# Power_Management.net
KiCad netlist of a schematic drawn in Altium Designer
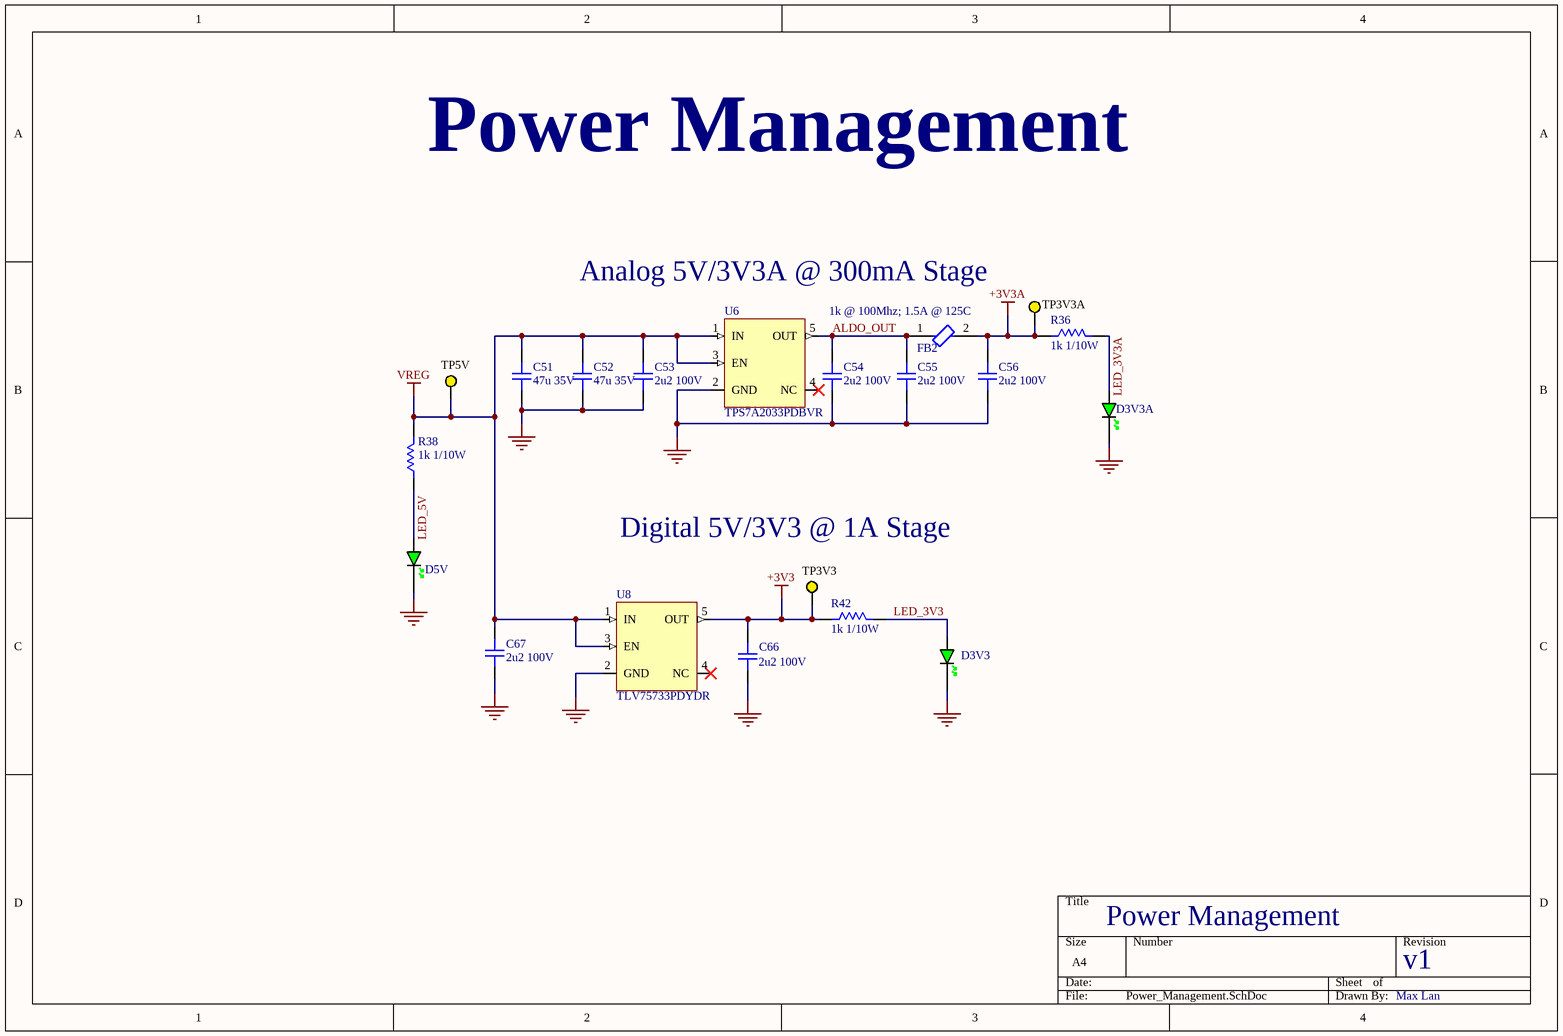
[diagram p0: Power_Management.SchDoc]

(export (version "E")
  (design (tool "Eeschema 10.0.6"))
  (components
    (comp (ref "C51")
      (value "47u 35V")
      (footprint "CAP_2220")
      (description "MLCC - SMD/SMT 2220 35VDC 47uF 20% X7R")
      (libsource (lib "Schematic-Lib-PhilsLab") (part "C5750X7R1V476M230KC"))
    )
    (comp (ref "C52")
      (value "47u 35V")
      (footprint "CAP_2220")
      (description "MLCC - SMD/SMT 2220 35VDC 47uF 20% X7R")
      (libsource (lib "Schematic-Lib-PhilsLab") (part "C5750X7R1V476M230KC"))
    )
    (comp (ref "C53")
      (value "2u2 100V")
      (footprint "CAP_1210")
      (description "Multilayer Ceramic Capacitors MLCC - SMD/SMT 100V 2.2uF X7R 1210 5% AEC-Q200")
      (fields
        (field (name "MANUFACTURER") "KEMET")
        (field (name "MANUFACTURER PART NUMBER") "C1210C225J1RACAUTO")
      )
      (libsource (lib "Schematic-Lib-PhilsLab") (part "C1210C225J1RACAUTO"))
    )
    (comp (ref "C54")
      (value "2u2 100V")
      (footprint "CAP_1210")
      (description "Multilayer Ceramic Capacitors MLCC - SMD/SMT 100V 2.2uF X7R 1210 5% AEC-Q200")
      (fields
        (field (name "MANUFACTURER") "KEMET")
        (field (name "MANUFACTURER PART NUMBER") "C1210C225J1RACAUTO")
      )
      (libsource (lib "Schematic-Lib-PhilsLab") (part "C1210C225J1RACAUTO"))
    )
    (comp (ref "C55")
      (value "2u2 100V")
      (footprint "CAP_1210")
      (description "Multilayer Ceramic Capacitors MLCC - SMD/SMT 100V 2.2uF X7R 1210 5% AEC-Q200")
      (fields
        (field (name "MANUFACTURER") "KEMET")
        (field (name "MANUFACTURER PART NUMBER") "C1210C225J1RACAUTO")
      )
      (libsource (lib "Schematic-Lib-PhilsLab") (part "C1210C225J1RACAUTO"))
    )
    (comp (ref "C56")
      (value "2u2 100V")
      (footprint "CAP_1210")
      (description "Multilayer Ceramic Capacitors MLCC - SMD/SMT 100V 2.2uF X7R 1210 5% AEC-Q200")
      (fields
        (field (name "MANUFACTURER") "KEMET")
        (field (name "MANUFACTURER PART NUMBER") "C1210C225J1RACAUTO")
      )
      (libsource (lib "Schematic-Lib-PhilsLab") (part "C1210C225J1RACAUTO"))
    )
    (comp (ref "C66")
      (value "2u2 100V")
      (footprint "CAP_1210")
      (description "Multilayer Ceramic Capacitors MLCC - SMD/SMT 100V 2.2uF X7R 1210 5% AEC-Q200")
      (fields
        (field (name "MANUFACTURER") "KEMET")
        (field (name "MANUFACTURER PART NUMBER") "C1210C225J1RACAUTO")
      )
      (libsource (lib "Schematic-Lib-PhilsLab") (part "C1210C225J1RACAUTO"))
    )
    (comp (ref "C67")
      (value "2u2 100V")
      (footprint "CAP_1210")
      (description "Multilayer Ceramic Capacitors MLCC - SMD/SMT 100V 2.2uF X7R 1210 5% AEC-Q200")
      (fields
        (field (name "MANUFACTURER") "KEMET")
        (field (name "MANUFACTURER PART NUMBER") "C1210C225J1RACAUTO")
      )
      (libsource (lib "Schematic-Lib-PhilsLab") (part "C1210C225J1RACAUTO"))
    )
    (comp (ref "D3V3")
      (value "GREEN")
      (footprint "LED_0603_GREEN")
      (description "LED 0603 GREEN SMD")
      (libsource (lib "Schematic-Lib-PhilsLab") (part "LED_0603_GREEN"))
    )
    (comp (ref "D3V3A")
      (value "GREEN")
      (footprint "LED_0603_GREEN")
      (description "LED 0603 GREEN SMD")
      (libsource (lib "Schematic-Lib-PhilsLab") (part "LED_0603_GREEN"))
    )
    (comp (ref "D5V")
      (value "GREEN")
      (footprint "LED_0603_GREEN")
      (description "LED 0603 GREEN SMD")
      (libsource (lib "Schematic-Lib-PhilsLab") (part "LED_0603_GREEN"))
    )
    (comp (ref "FB2")
      (value "1k @ 100Mhz; 1.5A @ 125C")
      (footprint "FP-MPZ2012-MFG")
      (description "FERRITE BEAD 1 KOHM 0805 1LN")
      (fields (field (name "TOLERANCE") "25%"))
      (libsource (lib "Altium Content Vault") (part "5f30dd21d616792df468990f7003faa"))
    )
    (comp (ref "R36")
      (value "1k 1/10W")
      (footprint "RES_0603")
      (description "Thick Film Resistors - SMD Res 0603 1k 1% 100mW TC100 low lead")
      (fields
        (field (name "MANUFACTURER") "Bourns")
        (field (name "MANUFACTURER PART NUMBER") "CR0603-FX-1001EPF")
      )
      (libsource (lib "Schematic-Lib-PhilsLab") (part "CR0603-FX-1001EPF"))
    )
    (comp (ref "R38")
      (value "1k 1/10W")
      (footprint "RES_0603")
      (description "Thick Film Resistors - SMD Res 0603 1k 1% 100mW TC100 low lead")
      (fields
        (field (name "MANUFACTURER") "Bourns")
        (field (name "MANUFACTURER PART NUMBER") "CR0603-FX-1001EPF")
      )
      (libsource (lib "Schematic-Lib-PhilsLab") (part "CR0603-FX-1001EPF"))
    )
    (comp (ref "R42")
      (value "1k 1/10W")
      (footprint "RES_0603")
      (description "Thick Film Resistors - SMD Res 0603 1k 1% 100mW TC100 low lead")
      (fields
        (field (name "MANUFACTURER") "Bourns")
        (field (name "MANUFACTURER PART NUMBER") "CR0603-FX-1001EPF")
      )
      (libsource (lib "Schematic-Lib-PhilsLab") (part "CR0603-FX-1001EPF"))
    )
    (comp (ref "TP3V3")
      (value "5014")
      (footprint "KSTN-5014_V")
      (description "Test Point, Yellow, Through Hole, RoHS, Bulk")
      (fields (field (name "MANUFACTURER") "Keystone"))
      (libsource (lib "Altium Content Vault") (part "TESTPOINT_YELLOW"))
    )
    (comp (ref "TP3V3A")
      (value "5014")
      (footprint "KSTN-5014_V")
      (description "Test Point, Yellow, Through Hole, RoHS, Bulk")
      (fields (field (name "MANUFACTURER") "Keystone"))
      (libsource (lib "Altium Content Vault") (part "TESTPOINT_YELLOW"))
    )
    (comp (ref "TP5V")
      (value "5014")
      (footprint "KSTN-5014_V")
      (description "Test Point, Yellow, Through Hole, RoHS, Bulk")
      (fields (field (name "MANUFACTURER") "Keystone"))
      (libsource (lib "Altium Content Vault") (part "TESTPOINT_YELLOW"))
    )
    (comp (ref "U6")
      (value "TPS7A2033PDBVR")
      (footprint "TPS7A2033PDBVR")
      (libsource (lib "Schematic-Lib-PhilsLab") (part "TPS7A2033PDBVR"))
    )
    (comp (ref "U8")
      (value "TLV75733PDYDR")
      (footprint "TLV75733PDYDR")
      (libsource (lib "Schematic-Lib-PhilsLab") (part "TLV75733PDYDR"))
    )
  )
  (nets
    (net (code "1") (name "+3V3") (class "Default")
      (node (ref "C66") (pin "2") (pinfunction "2_2") (pintype "passive"))
      (node (ref "R42") (pin "1") (pinfunction "1_1") (pintype "passive"))
      (node (ref "TP3V3") (pin "1") (pinfunction "1_1") (pintype "passive"))
      (node (ref "U8") (pin "5") (pinfunction "OUT_5") (pintype "output"))
    )
    (net (code "2") (name "+3V3A") (class "Default")
      (node (ref "C56") (pin "2") (pinfunction "2_2") (pintype "passive"))
      (node (ref "FB2") (pin "2") (pinfunction "2_2") (pintype "passive"))
      (node (ref "R36") (pin "1") (pinfunction "1_1") (pintype "passive"))
      (node (ref "TP3V3A") (pin "1") (pinfunction "1_1") (pintype "passive"))
    )
    (net (code "3") (name "/ALDO_OUT") (class "Default")
      (node (ref "C54") (pin "2") (pinfunction "2_2") (pintype "passive"))
      (node (ref "C55") (pin "2") (pinfunction "2_2") (pintype "passive"))
      (node (ref "FB2") (pin "1") (pinfunction "1_1") (pintype "passive"))
      (node (ref "U6") (pin "5") (pinfunction "OUT_5") (pintype "output"))
    )
    (net (code "4") (name "/LED_3V3") (class "Default")
      (node (ref "D3V3") (pin "A") (pinfunction "A_A") (pintype "passive"))
      (node (ref "R42") (pin "2") (pinfunction "2_2") (pintype "passive"))
    )
    (net (code "5") (name "/LED_3V3A") (class "Default")
      (node (ref "D3V3A") (pin "A") (pinfunction "A_A") (pintype "passive"))
      (node (ref "R36") (pin "2") (pinfunction "2_2") (pintype "passive"))
    )
    (net (code "6") (name "/LED_5V") (class "Default")
      (node (ref "D5V") (pin "A") (pinfunction "A_A") (pintype "passive"))
      (node (ref "R38") (pin "2") (pinfunction "2_2") (pintype "passive"))
    )
    (net (code "7") (name "GND") (class "Default")
      (node (ref "C51") (pin "1") (pinfunction "1_1") (pintype "passive"))
      (node (ref "C52") (pin "1") (pinfunction "1_1") (pintype "passive"))
      (node (ref "C53") (pin "1") (pinfunction "1_1") (pintype "passive"))
      (node (ref "C54") (pin "1") (pinfunction "1_1") (pintype "passive"))
      (node (ref "C55") (pin "1") (pinfunction "1_1") (pintype "passive"))
      (node (ref "C56") (pin "1") (pinfunction "1_1") (pintype "passive"))
      (node (ref "C66") (pin "1") (pinfunction "1_1") (pintype "passive"))
      (node (ref "C67") (pin "1") (pinfunction "1_1") (pintype "passive"))
      (node (ref "D3V3") (pin "K") (pinfunction "K_K") (pintype "passive"))
      (node (ref "D3V3A") (pin "K") (pinfunction "K_K") (pintype "passive"))
      (node (ref "D5V") (pin "K") (pinfunction "K_K") (pintype "passive"))
      (node (ref "U6") (pin "2") (pinfunction "GND_2") (pintype "passive"))
      (node (ref "U8") (pin "2") (pinfunction "GND_2") (pintype "passive"))
    )
    (net (code "8") (name "VREG") (class "Default")
      (node (ref "C51") (pin "2") (pinfunction "2_2") (pintype "passive"))
      (node (ref "C52") (pin "2") (pinfunction "2_2") (pintype "passive"))
      (node (ref "C53") (pin "2") (pinfunction "2_2") (pintype "passive"))
      (node (ref "C67") (pin "2") (pinfunction "2_2") (pintype "passive"))
      (node (ref "R38") (pin "1") (pinfunction "1_1") (pintype "passive"))
      (node (ref "TP5V") (pin "1") (pinfunction "1_1") (pintype "passive"))
      (node (ref "U6") (pin "1") (pinfunction "IN_1") (pintype "input"))
      (node (ref "U6") (pin "3") (pinfunction "EN_3") (pintype "input"))
      (node (ref "U8") (pin "1") (pinfunction "IN_1") (pintype "input"))
      (node (ref "U8") (pin "3") (pinfunction "EN_3") (pintype "input"))
    )
    (net (code "9") (name "unconnected-(U6-NC-Pad4)") (class "Default")
      (node (ref "U6") (pin "4") (pinfunction "NC_4") (pintype "passive+no_connect"))
    )
    (net (code "10") (name "unconnected-(U8-NC-Pad4)") (class "Default")
      (node (ref "U8") (pin "4") (pinfunction "NC_4") (pintype "passive+no_connect"))
    )
  )
)
